# untitled2.net
KiCad netlist of a schematic drawn in EAGLE
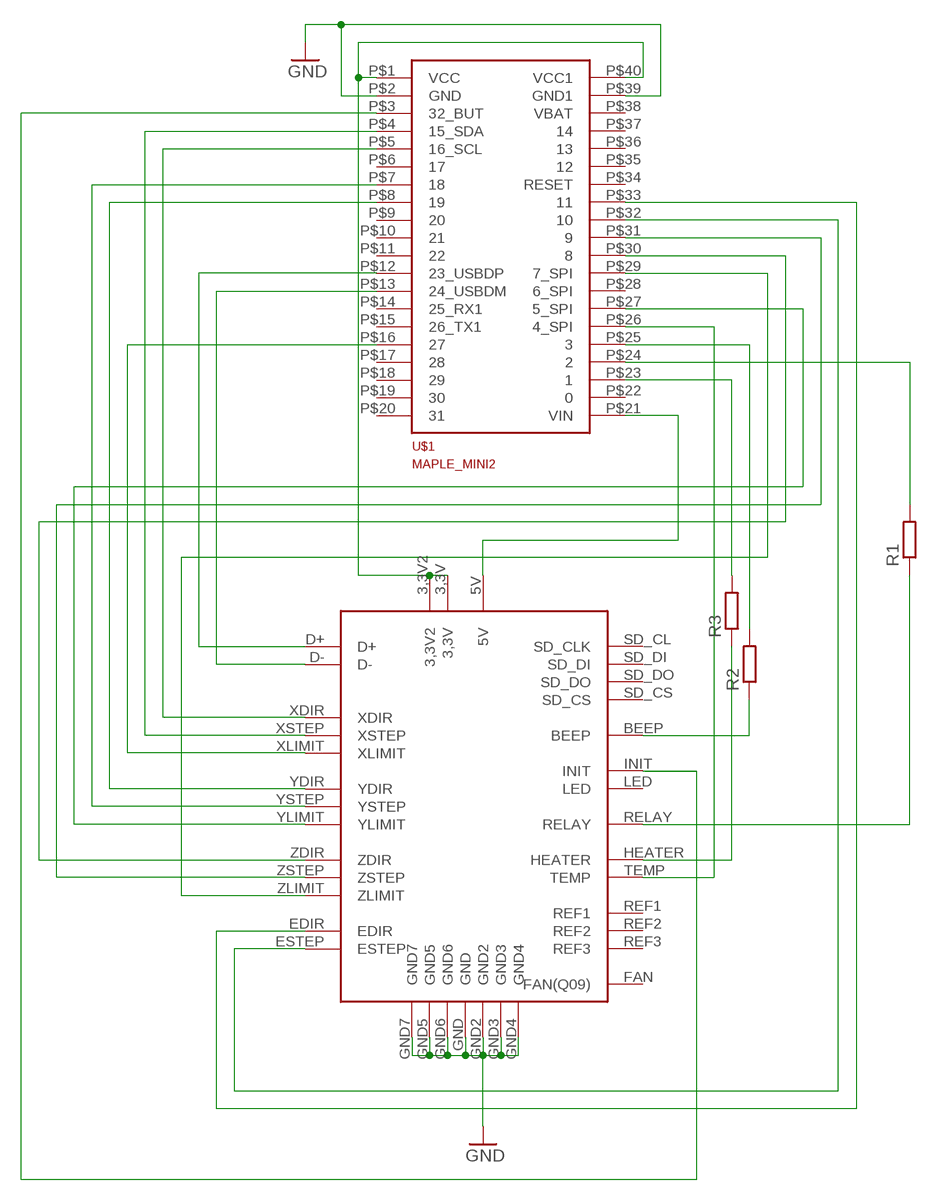
[diagram p0: schematic, sheet 1]

(export (version "E")
  (design (tool "Eeschema 10.0.6"))
  (components
    (comp (ref "R1")
      (value "R-EU_0204/7")
      (footprint "eagle-import:0204_7")
      (libsource (lib "eagle-import") (part "R-EU_0204/7"))
    )
    (comp (ref "R2")
      (value "R-EU_0204/7")
      (footprint "eagle-import:0204_7")
      (libsource (lib "eagle-import") (part "R-EU_0204/7"))
    )
    (comp (ref "R3")
      (value "R-EU_0204/7")
      (footprint "eagle-import:0204_7")
      (libsource (lib "eagle-import") (part "R-EU_0204/7"))
    )
    (comp (ref "U$1")
      (value "MAPLE_MINI2")
      (footprint "eagle-import:MAPLE_MINI")
      (libsource (lib "eagle-import") (part "MAPLE_MINI2"))
    )
    (comp (ref "U$2")
      (value "CETUS_CONTROLLER")
      (footprint "eagle-import:CETUS_CONTROLLER")
      (libsource (lib "eagle-import") (part "CETUS_CONTROLLER"))
    )
  )
  (nets
    (net (code "1") (name "GND") (class "Default")
      (node (ref "U$1") (pin "P$2") (pinfunction "GND_P$2") (pintype "bidirectional"))
      (node (ref "U$1") (pin "P$39") (pinfunction "GND1_P$39") (pintype "bidirectional"))
      (node (ref "U$2") (pin "GND") (pinfunction "GND_GND") (pintype "power_in"))
      (node (ref "U$2") (pin "GND2") (pinfunction "GND2_GND2") (pintype "bidirectional"))
      (node (ref "U$2") (pin "GND3") (pinfunction "GND3_GND3") (pintype "bidirectional"))
      (node (ref "U$2") (pin "GND4") (pinfunction "GND4_GND4") (pintype "bidirectional"))
      (node (ref "U$2") (pin "GND5") (pinfunction "GND5_GND5") (pintype "bidirectional"))
      (node (ref "U$2") (pin "GND6") (pinfunction "GND6_GND6") (pintype "bidirectional"))
      (node (ref "U$2") (pin "GND7") (pinfunction "GND7_GND7") (pintype "bidirectional"))
    )
    (net (code "2") (name "Net-(R1-Pad1)") (class "Default")
      (node (ref "R1") (pin "1") (pinfunction "1_1") (pintype "passive"))
      (node (ref "U$2") (pin "RELAY") (pinfunction "RELAY_RELAY") (pintype "bidirectional"))
    )
    (net (code "3") (name "Net-(R2-Pad1)") (class "Default")
      (node (ref "R2") (pin "1") (pinfunction "1_1") (pintype "passive"))
      (node (ref "U$2") (pin "BEEP") (pinfunction "BEEP_BEEP") (pintype "bidirectional"))
    )
    (net (code "4") (name "Net-(R3-Pad1)") (class "Default")
      (node (ref "R3") (pin "1") (pinfunction "1_1") (pintype "passive"))
      (node (ref "U$2") (pin "HEATER") (pinfunction "HEATER_HEATER") (pintype "bidirectional"))
    )
    (net (code "5") (name "Net-(U$1-1)") (class "Default")
      (node (ref "R3") (pin "2") (pinfunction "2_2") (pintype "passive"))
      (node (ref "U$1") (pin "P$23") (pinfunction "1_P$23") (pintype "bidirectional"))
    )
    (net (code "6") (name "Net-(U$1-2)") (class "Default")
      (node (ref "R1") (pin "2") (pinfunction "2_2") (pintype "passive"))
      (node (ref "U$1") (pin "P$24") (pinfunction "2_P$24") (pintype "bidirectional"))
    )
    (net (code "7") (name "Net-(U$1-3)") (class "Default")
      (node (ref "R2") (pin "2") (pinfunction "2_2") (pintype "passive"))
      (node (ref "U$1") (pin "P$25") (pinfunction "3_P$25") (pintype "bidirectional"))
    )
    (net (code "8") (name "Net-(U$1-4_SPI)") (class "Default")
      (node (ref "U$1") (pin "P$26") (pinfunction "4_SPI_P$26") (pintype "bidirectional"))
      (node (ref "U$2") (pin "TEMP") (pinfunction "TEMP_TEMP") (pintype "bidirectional"))
    )
    (net (code "9") (name "Net-(U$1-5_SPI)") (class "Default")
      (node (ref "U$1") (pin "P$27") (pinfunction "5_SPI_P$27") (pintype "bidirectional"))
      (node (ref "U$2") (pin "YLIMIT") (pinfunction "YLIMIT_YLIMIT") (pintype "bidirectional"))
    )
    (net (code "10") (name "Net-(U$1-7_SPI)") (class "Default")
      (node (ref "U$1") (pin "P$29") (pinfunction "7_SPI_P$29") (pintype "bidirectional"))
      (node (ref "U$2") (pin "ZLIMIT") (pinfunction "ZLIMIT_ZLIMIT") (pintype "bidirectional"))
    )
    (net (code "11") (name "Net-(U$1-8)") (class "Default")
      (node (ref "U$1") (pin "P$30") (pinfunction "8_P$30") (pintype "bidirectional"))
      (node (ref "U$2") (pin "ZDIR") (pinfunction "ZDIR_ZDIR") (pintype "bidirectional"))
    )
    (net (code "12") (name "Net-(U$1-9)") (class "Default")
      (node (ref "U$1") (pin "P$31") (pinfunction "9_P$31") (pintype "bidirectional"))
      (node (ref "U$2") (pin "ZSTEP") (pinfunction "ZSTEP_ZSTEP") (pintype "bidirectional"))
    )
    (net (code "13") (name "Net-(U$1-10)") (class "Default")
      (node (ref "U$1") (pin "P$32") (pinfunction "10_P$32") (pintype "bidirectional"))
      (node (ref "U$2") (pin "ESTEP") (pinfunction "ESTEP_ESTEP") (pintype "bidirectional"))
    )
    (net (code "14") (name "Net-(U$1-11)") (class "Default")
      (node (ref "U$1") (pin "P$33") (pinfunction "11_P$33") (pintype "bidirectional"))
      (node (ref "U$2") (pin "EDIR") (pinfunction "EDIR_EDIR") (pintype "bidirectional"))
    )
    (net (code "15") (name "Net-(U$1-15_SDA)") (class "Default")
      (node (ref "U$1") (pin "P$4") (pinfunction "15_SDA_P$4") (pintype "bidirectional"))
      (node (ref "U$2") (pin "XSTEP") (pinfunction "XSTEP_XSTEP") (pintype "bidirectional"))
    )
    (net (code "16") (name "Net-(U$1-16_SCL)") (class "Default")
      (node (ref "U$1") (pin "P$5") (pinfunction "16_SCL_P$5") (pintype "bidirectional"))
      (node (ref "U$2") (pin "XDIR") (pinfunction "XDIR_XDIR") (pintype "bidirectional"))
    )
    (net (code "17") (name "Net-(U$1-18)") (class "Default")
      (node (ref "U$1") (pin "P$7") (pinfunction "18_P$7") (pintype "bidirectional"))
      (node (ref "U$2") (pin "YSTEP") (pinfunction "YSTEP_YSTEP") (pintype "bidirectional"))
    )
    (net (code "18") (name "Net-(U$1-19)") (class "Default")
      (node (ref "U$1") (pin "P$8") (pinfunction "19_P$8") (pintype "bidirectional"))
      (node (ref "U$2") (pin "YDIR") (pinfunction "YDIR_YDIR") (pintype "bidirectional"))
    )
    (net (code "19") (name "Net-(U$1-23_USBDP)") (class "Default")
      (node (ref "U$1") (pin "P$12") (pinfunction "23_USBDP_P$12") (pintype "bidirectional"))
      (node (ref "U$2") (pin "D+") (pinfunction "D+_D+") (pintype "bidirectional"))
    )
    (net (code "20") (name "Net-(U$1-24_USBDM)") (class "Default")
      (node (ref "U$1") (pin "P$13") (pinfunction "24_USBDM_P$13") (pintype "bidirectional"))
      (node (ref "U$2") (pin "D-") (pinfunction "D-_D-") (pintype "bidirectional"))
    )
    (net (code "21") (name "Net-(U$1-27)") (class "Default")
      (node (ref "U$1") (pin "P$16") (pinfunction "27_P$16") (pintype "bidirectional"))
      (node (ref "U$2") (pin "XLIMIT") (pinfunction "XLIMIT_XLIMIT") (pintype "bidirectional"))
    )
    (net (code "22") (name "Net-(U$1-32_BUT)") (class "Default")
      (node (ref "U$1") (pin "P$3") (pinfunction "32_BUT_P$3") (pintype "bidirectional"))
      (node (ref "U$2") (pin "INIT") (pinfunction "INIT_INIT") (pintype "bidirectional"))
    )
    (net (code "23") (name "Net-(U$1-VCC)") (class "Default")
      (node (ref "U$1") (pin "P$1") (pinfunction "VCC_P$1") (pintype "bidirectional"))
      (node (ref "U$1") (pin "P$40") (pinfunction "VCC1_P$40") (pintype "bidirectional"))
      (node (ref "U$2") (pin "3,3V") (pinfunction "3,3V_3,3V") (pintype "power_in"))
      (node (ref "U$2") (pin "3,3V2") (pinfunction "3,3V2_3,3V2") (pintype "power_in"))
    )
    (net (code "24") (name "Net-(U$1-VIN)") (class "Default")
      (node (ref "U$1") (pin "P$21") (pinfunction "VIN_P$21") (pintype "bidirectional"))
      (node (ref "U$2") (pin "5V") (pinfunction "5V_5V") (pintype "power_in"))
    )
    (net (code "25") (name "unconnected-(U$1-0-PadP$22)") (class "Default")
      (node (ref "U$1") (pin "P$22") (pinfunction "0_P$22") (pintype "bidirectional"))
    )
    (net (code "26") (name "unconnected-(U$1-6_SPI-PadP$28)") (class "Default")
      (node (ref "U$1") (pin "P$28") (pinfunction "6_SPI_P$28") (pintype "bidirectional"))
    )
    (net (code "27") (name "unconnected-(U$1-12-PadP$35)") (class "Default")
      (node (ref "U$1") (pin "P$35") (pinfunction "12_P$35") (pintype "bidirectional"))
    )
    (net (code "28") (name "unconnected-(U$1-13-PadP$36)") (class "Default")
      (node (ref "U$1") (pin "P$36") (pinfunction "13_P$36") (pintype "bidirectional"))
    )
    (net (code "29") (name "unconnected-(U$1-14-PadP$37)") (class "Default")
      (node (ref "U$1") (pin "P$37") (pinfunction "14_P$37") (pintype "bidirectional"))
    )
    (net (code "30") (name "unconnected-(U$1-17-PadP$6)") (class "Default")
      (node (ref "U$1") (pin "P$6") (pinfunction "17_P$6") (pintype "bidirectional"))
    )
    (net (code "31") (name "unconnected-(U$1-20-PadP$9)") (class "Default")
      (node (ref "U$1") (pin "P$9") (pinfunction "20_P$9") (pintype "bidirectional"))
    )
    (net (code "32") (name "unconnected-(U$1-21-PadP$10)") (class "Default")
      (node (ref "U$1") (pin "P$10") (pinfunction "21_P$10") (pintype "bidirectional"))
    )
    (net (code "33") (name "unconnected-(U$1-22-PadP$11)") (class "Default")
      (node (ref "U$1") (pin "P$11") (pinfunction "22_P$11") (pintype "bidirectional"))
    )
    (net (code "34") (name "unconnected-(U$1-25_RX1-PadP$14)") (class "Default")
      (node (ref "U$1") (pin "P$14") (pinfunction "25_RX1_P$14") (pintype "bidirectional"))
    )
    (net (code "35") (name "unconnected-(U$1-26_TX1-PadP$15)") (class "Default")
      (node (ref "U$1") (pin "P$15") (pinfunction "26_TX1_P$15") (pintype "bidirectional"))
    )
    (net (code "36") (name "unconnected-(U$1-28-PadP$17)") (class "Default")
      (node (ref "U$1") (pin "P$17") (pinfunction "28_P$17") (pintype "bidirectional"))
    )
    (net (code "37") (name "unconnected-(U$1-29-PadP$18)") (class "Default")
      (node (ref "U$1") (pin "P$18") (pinfunction "29_P$18") (pintype "bidirectional"))
    )
    (net (code "38") (name "unconnected-(U$1-30-PadP$19)") (class "Default")
      (node (ref "U$1") (pin "P$19") (pinfunction "30_P$19") (pintype "bidirectional"))
    )
    (net (code "39") (name "unconnected-(U$1-31-PadP$20)") (class "Default")
      (node (ref "U$1") (pin "P$20") (pinfunction "31_P$20") (pintype "bidirectional"))
    )
    (net (code "40") (name "unconnected-(U$1-RESET-PadP$34)") (class "Default")
      (node (ref "U$1") (pin "P$34") (pinfunction "RESET_P$34") (pintype "bidirectional"))
    )
    (net (code "41") (name "unconnected-(U$1-VBAT-PadP$38)") (class "Default")
      (node (ref "U$1") (pin "P$38") (pinfunction "VBAT_P$38") (pintype "bidirectional"))
    )
    (net (code "42") (name "unconnected-(U$2-FAN(Q09)-PadFAN)") (class "Default")
      (node (ref "U$2") (pin "FAN") (pinfunction "FAN(Q09)_FAN") (pintype "bidirectional"))
    )
    (net (code "43") (name "unconnected-(U$2-PadLED)") (class "Default")
      (node (ref "U$2") (pin "LED") (pinfunction "LED_LED") (pintype "bidirectional"))
    )
    (net (code "44") (name "unconnected-(U$2-PadREF1)") (class "Default")
      (node (ref "U$2") (pin "REF1") (pinfunction "REF1_REF1") (pintype "bidirectional"))
    )
    (net (code "45") (name "unconnected-(U$2-PadREF2)") (class "Default")
      (node (ref "U$2") (pin "REF2") (pinfunction "REF2_REF2") (pintype "bidirectional"))
    )
    (net (code "46") (name "unconnected-(U$2-PadREF3)") (class "Default")
      (node (ref "U$2") (pin "REF3") (pinfunction "REF3_REF3") (pintype "bidirectional"))
    )
    (net (code "47") (name "unconnected-(U$2-PadSD_CS)") (class "Default")
      (node (ref "U$2") (pin "SD_CS") (pinfunction "SD_CS_SD_CS") (pintype "bidirectional"))
    )
    (net (code "48") (name "unconnected-(U$2-PadSD_DI)") (class "Default")
      (node (ref "U$2") (pin "SD_DI") (pinfunction "SD_DI_SD_DI") (pintype "bidirectional"))
    )
    (net (code "49") (name "unconnected-(U$2-PadSD_DO)") (class "Default")
      (node (ref "U$2") (pin "SD_DO") (pinfunction "SD_DO_SD_DO") (pintype "bidirectional"))
    )
    (net (code "50") (name "unconnected-(U$2-SD_CLK-PadSD_CL)") (class "Default")
      (node (ref "U$2") (pin "SD_CL") (pinfunction "SD_CLK_SD_CL") (pintype "bidirectional"))
    )
  )
)
